# Voeding.net
KiCad netlist of a schematic drawn in Altium Designer
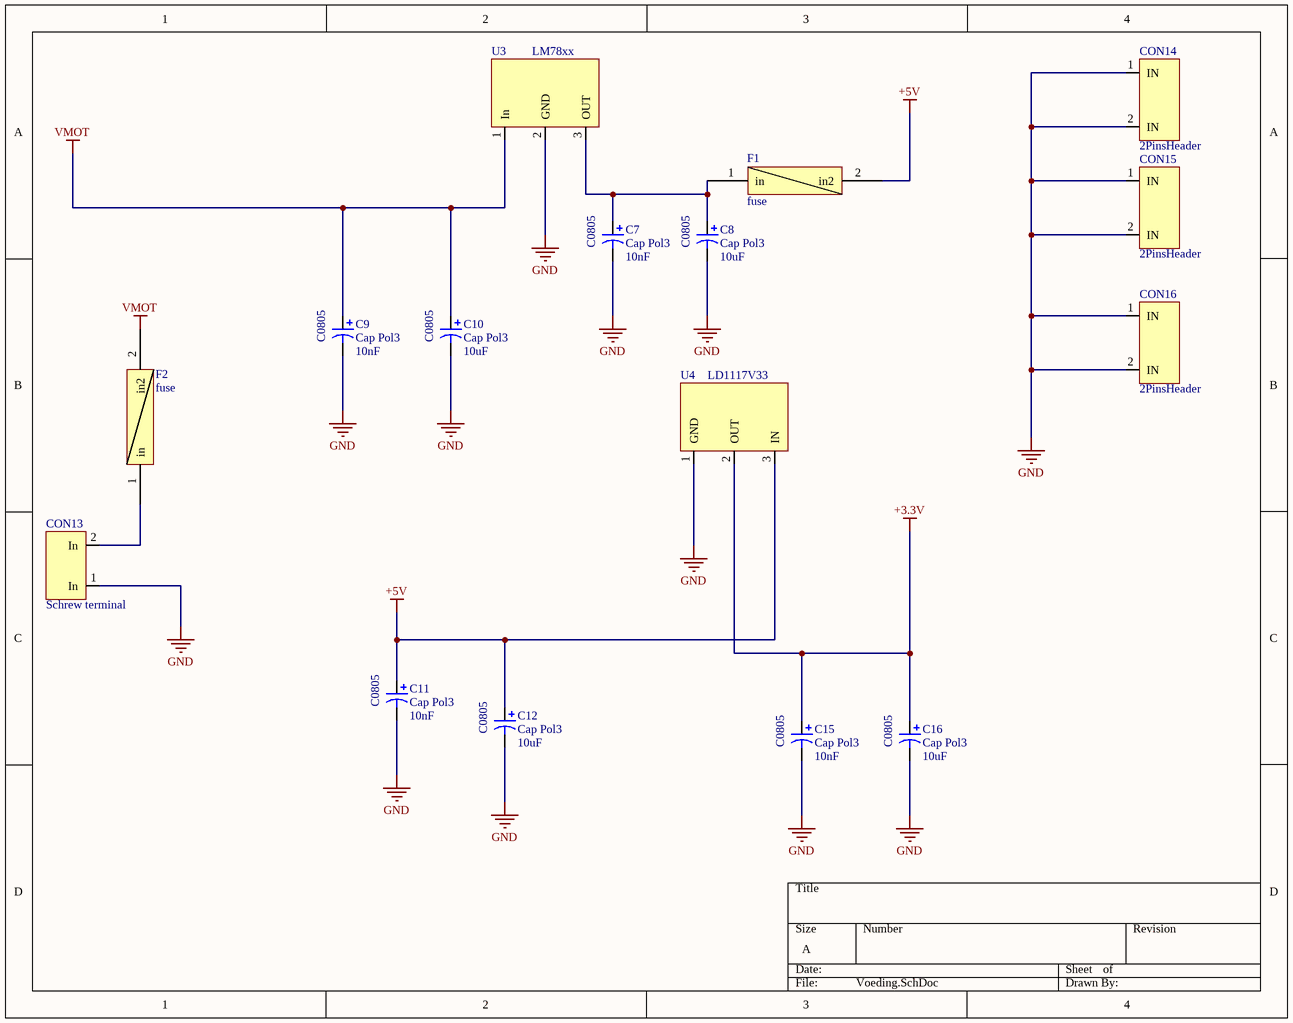
[diagram p0: Voeding.SchDoc]

(export (version "E")
  (design (tool "Eeschema 10.0.6"))
  (components
    (comp (ref "C7")
      (value "Cap Pol3")
      (footprint "C0805")
      (description "Polarized Capacitor (Surface Mount)")
      (fields
        (field (name "PACKAGEREFERENCE") "C0805")
        (field (name "ALTIUM_VALUE") "10nF")
        (field (name "PUBLISHER") "Altium Limited")
      )
      (libsource (lib "Miscellaneous Devices") (part "Cap Pol3"))
    )
    (comp (ref "C8")
      (value "Cap Pol3")
      (footprint "C0805")
      (description "Polarized Capacitor (Surface Mount)")
      (fields
        (field (name "PACKAGEREFERENCE") "C0805")
        (field (name "ALTIUM_VALUE") "10uF")
        (field (name "PUBLISHER") "Altium Limited")
      )
      (libsource (lib "Miscellaneous Devices") (part "Cap Pol3"))
    )
    (comp (ref "C9")
      (value "Cap Pol3")
      (footprint "C0805")
      (description "Polarized Capacitor (Surface Mount)")
      (fields
        (field (name "PACKAGEREFERENCE") "C0805")
        (field (name "ALTIUM_VALUE") "10nF")
        (field (name "PUBLISHER") "Altium Limited")
      )
      (libsource (lib "Miscellaneous Devices") (part "Cap Pol3"))
    )
    (comp (ref "C10")
      (value "Cap Pol3")
      (footprint "C0805")
      (description "Polarized Capacitor (Surface Mount)")
      (fields
        (field (name "PACKAGEREFERENCE") "C0805")
        (field (name "ALTIUM_VALUE") "10uF")
        (field (name "PUBLISHER") "Altium Limited")
      )
      (libsource (lib "Miscellaneous Devices") (part "Cap Pol3"))
    )
    (comp (ref "C11")
      (value "Cap Pol3")
      (footprint "C0805")
      (description "Polarized Capacitor (Surface Mount)")
      (fields
        (field (name "PACKAGEREFERENCE") "C0805")
        (field (name "ALTIUM_VALUE") "10nF")
        (field (name "PUBLISHER") "Altium Limited")
      )
      (libsource (lib "Miscellaneous Devices") (part "Cap Pol3"))
    )
    (comp (ref "C12")
      (value "Cap Pol3")
      (footprint "C0805")
      (description "Polarized Capacitor (Surface Mount)")
      (fields
        (field (name "PACKAGEREFERENCE") "C0805")
        (field (name "ALTIUM_VALUE") "10uF")
        (field (name "PUBLISHER") "Altium Limited")
      )
      (libsource (lib "Miscellaneous Devices") (part "Cap Pol3"))
    )
    (comp (ref "C15")
      (value "Cap Pol3")
      (footprint "C0805")
      (description "Polarized Capacitor (Surface Mount)")
      (fields
        (field (name "PACKAGEREFERENCE") "C0805")
        (field (name "ALTIUM_VALUE") "10nF")
        (field (name "PUBLISHER") "Altium Limited")
      )
      (libsource (lib "Miscellaneous Devices") (part "Cap Pol3"))
    )
    (comp (ref "C16")
      (value "Cap Pol3")
      (footprint "C0805")
      (description "Polarized Capacitor (Surface Mount)")
      (fields
        (field (name "PACKAGEREFERENCE") "C0805")
        (field (name "ALTIUM_VALUE") "10uF")
        (field (name "PUBLISHER") "Altium Limited")
      )
      (libsource (lib "Miscellaneous Devices") (part "Cap Pol3"))
    )
    (comp (ref "CON13")
      (value "Schrew terminal")
      (footprint "ScrewTerminal")
      (libsource (lib "ScewTerminal") (part "Schrew terminal"))
    )
    (comp (ref "CON14")
      (value "2PinsHeader")
      (footprint "2PinsHeader")
      (libsource (lib "2pinsHeader") (part "2PinsHeader"))
    )
    (comp (ref "CON15")
      (value "2PinsHeader")
      (footprint "2PinsHeader")
      (libsource (lib "2pinsHeader") (part "2PinsHeader"))
    )
    (comp (ref "CON16")
      (value "2PinsHeader")
      (footprint "2PinsHeader")
      (libsource (lib "2pinsHeader") (part "2PinsHeader"))
    )
    (comp (ref "F1")
      (value "fuse")
      (footprint "Fuse")
      (description "fuse ptc")
      (libsource (lib "fuse") (part "Component_1"))
    )
    (comp (ref "F2")
      (value "fuse")
      (footprint "Fuse")
      (description "fuse ptc")
      (libsource (lib "") (part "Component_1_1"))
    )
    (comp (ref "U3") (value "LM78xx") (footprint "LM78xx") (libsource (lib "LM78xx") (part "LM78xx")))
    (comp (ref "U4")
      (value "LD1117V33")
      (footprint "LD117vxx")
      (libsource (lib "ATMEGA126") (part "LD1117V33"))
    )
  )
  (nets
    (net (code "1") (name "+3.3V") (class "Default")
      (node (ref "C15") (pin "1") (pinfunction "1_1") (pintype "passive"))
      (node (ref "C16") (pin "1") (pinfunction "1_1") (pintype "passive"))
      (node (ref "U4") (pin "2") (pinfunction "OUT_2") (pintype "passive"))
    )
    (net (code "2") (name "+5V") (class "Default")
      (node (ref "C11") (pin "1") (pinfunction "1_1") (pintype "passive"))
      (node (ref "C12") (pin "1") (pinfunction "1_1") (pintype "passive"))
      (node (ref "F1") (pin "2") (pinfunction "in2_2") (pintype "passive"))
      (node (ref "U4") (pin "3") (pinfunction "IN_3") (pintype "passive"))
    )
    (net (code "3") (name "GND") (class "Default")
      (node (ref "C10") (pin "2") (pinfunction "2_2") (pintype "passive"))
      (node (ref "C11") (pin "2") (pinfunction "2_2") (pintype "passive"))
      (node (ref "C12") (pin "2") (pinfunction "2_2") (pintype "passive"))
      (node (ref "C15") (pin "2") (pinfunction "2_2") (pintype "passive"))
      (node (ref "C16") (pin "2") (pinfunction "2_2") (pintype "passive"))
      (node (ref "C7") (pin "2") (pinfunction "2_2") (pintype "passive"))
      (node (ref "C8") (pin "2") (pinfunction "2_2") (pintype "passive"))
      (node (ref "C9") (pin "2") (pinfunction "2_2") (pintype "passive"))
      (node (ref "CON13") (pin "1") (pinfunction "In_1") (pintype "passive"))
      (node (ref "CON14") (pin "1") (pinfunction "IN_1") (pintype "passive"))
      (node (ref "CON14") (pin "2") (pinfunction "IN_2") (pintype "passive"))
      (node (ref "CON15") (pin "1") (pinfunction "IN_1") (pintype "passive"))
      (node (ref "CON15") (pin "2") (pinfunction "IN_2") (pintype "passive"))
      (node (ref "CON16") (pin "1") (pinfunction "IN_1") (pintype "passive"))
      (node (ref "CON16") (pin "2") (pinfunction "IN_2") (pintype "passive"))
      (node (ref "U3") (pin "2") (pinfunction "GND_2") (pintype "passive"))
      (node (ref "U4") (pin "1") (pinfunction "GND_1") (pintype "passive"))
    )
    (net (code "4") (name "Net-(F1-in)") (class "Default")
      (node (ref "C7") (pin "1") (pinfunction "1_1") (pintype "passive"))
      (node (ref "C8") (pin "1") (pinfunction "1_1") (pintype "passive"))
      (node (ref "F1") (pin "1") (pinfunction "in_1") (pintype "passive"))
      (node (ref "U3") (pin "3") (pinfunction "OUT_3") (pintype "passive"))
    )
    (net (code "5") (name "Net-(F2-in)") (class "Default")
      (node (ref "CON13") (pin "2") (pinfunction "In_2") (pintype "passive"))
      (node (ref "F2") (pin "1") (pinfunction "in_1") (pintype "passive"))
    )
    (net (code "6") (name "VMOT") (class "Default")
      (node (ref "C10") (pin "1") (pinfunction "1_1") (pintype "passive"))
      (node (ref "C9") (pin "1") (pinfunction "1_1") (pintype "passive"))
      (node (ref "F2") (pin "2") (pinfunction "in2_2") (pintype "passive"))
      (node (ref "U3") (pin "1") (pinfunction "In_1") (pintype "passive"))
    )
  )
)
